# Sheet2.net
KiCad netlist of a schematic drawn in Altium Designer
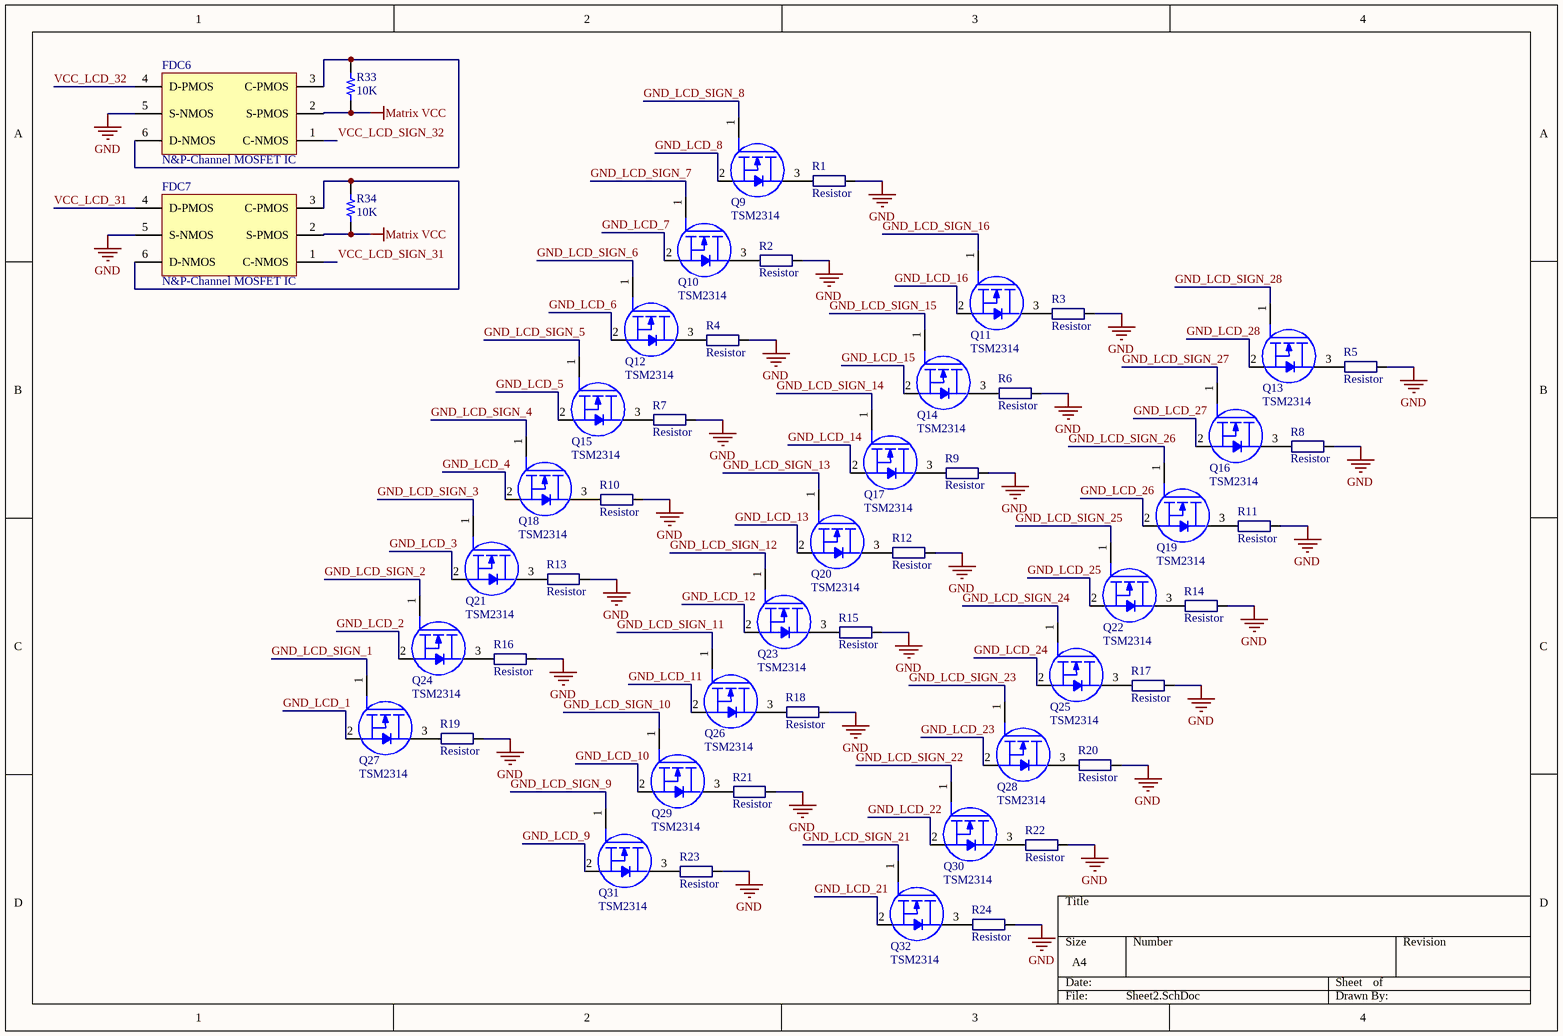
[diagram p0: Sheet2.SchDoc]

(export (version "E")
  (design (tool "Eeschema 10.0.6"))
  (components
    (comp (ref "FDC6")
      (value "N&P-Channel MOSFET IC")
      (footprint "SSOT-6")
      (libsource (lib "IC Chips") (part "FDC633C"))
    )
    (comp (ref "FDC7")
      (value "N&P-Channel MOSFET IC")
      (footprint "SSOT-6")
      (libsource (lib "IC Chips") (part "FDC633C"))
    )
    (comp (ref "Q9")
      (value "TSM2314")
      (footprint "SOT95P280X130-3N")
      (description "N-Channel MOSFET")
      (libsource (lib "OVLib") (part "MOSFET_N_GSD"))
    )
    (comp (ref "Q10")
      (value "TSM2314")
      (footprint "SOT95P280X130-3N")
      (description "N-Channel MOSFET")
      (libsource (lib "OVLib") (part "MOSFET_N_GSD"))
    )
    (comp (ref "Q11")
      (value "TSM2314")
      (footprint "SOT95P280X130-3N")
      (description "N-Channel MOSFET")
      (libsource (lib "OVLib") (part "MOSFET_N_GSD"))
    )
    (comp (ref "Q12")
      (value "TSM2314")
      (footprint "SOT95P280X130-3N")
      (description "N-Channel MOSFET")
      (libsource (lib "OVLib") (part "MOSFET_N_GSD"))
    )
    (comp (ref "Q13")
      (value "TSM2314")
      (footprint "SOT95P280X130-3N")
      (description "N-Channel MOSFET")
      (libsource (lib "OVLib") (part "MOSFET_N_GSD"))
    )
    (comp (ref "Q14")
      (value "TSM2314")
      (footprint "SOT95P280X130-3N")
      (description "N-Channel MOSFET")
      (libsource (lib "OVLib") (part "MOSFET_N_GSD"))
    )
    (comp (ref "Q15")
      (value "TSM2314")
      (footprint "SOT95P280X130-3N")
      (description "N-Channel MOSFET")
      (libsource (lib "OVLib") (part "MOSFET_N_GSD"))
    )
    (comp (ref "Q16")
      (value "TSM2314")
      (footprint "SOT95P280X130-3N")
      (description "N-Channel MOSFET")
      (libsource (lib "OVLib") (part "MOSFET_N_GSD"))
    )
    (comp (ref "Q17")
      (value "TSM2314")
      (footprint "SOT95P280X130-3N")
      (description "N-Channel MOSFET")
      (libsource (lib "OVLib") (part "MOSFET_N_GSD"))
    )
    (comp (ref "Q18")
      (value "TSM2314")
      (footprint "SOT95P280X130-3N")
      (description "N-Channel MOSFET")
      (libsource (lib "OVLib") (part "MOSFET_N_GSD"))
    )
    (comp (ref "Q19")
      (value "TSM2314")
      (footprint "SOT95P280X130-3N")
      (description "N-Channel MOSFET")
      (libsource (lib "OVLib") (part "MOSFET_N_GSD"))
    )
    (comp (ref "Q20")
      (value "TSM2314")
      (footprint "SOT95P280X130-3N")
      (description "N-Channel MOSFET")
      (libsource (lib "OVLib") (part "MOSFET_N_GSD"))
    )
    (comp (ref "Q21")
      (value "TSM2314")
      (footprint "SOT95P280X130-3N")
      (description "N-Channel MOSFET")
      (libsource (lib "OVLib") (part "MOSFET_N_GSD"))
    )
    (comp (ref "Q22")
      (value "TSM2314")
      (footprint "SOT95P280X130-3N")
      (description "N-Channel MOSFET")
      (libsource (lib "OVLib") (part "MOSFET_N_GSD"))
    )
    (comp (ref "Q23")
      (value "TSM2314")
      (footprint "SOT95P280X130-3N")
      (description "N-Channel MOSFET")
      (libsource (lib "OVLib") (part "MOSFET_N_GSD"))
    )
    (comp (ref "Q24")
      (value "TSM2314")
      (footprint "SOT95P280X130-3N")
      (description "N-Channel MOSFET")
      (libsource (lib "OVLib") (part "MOSFET_N_GSD"))
    )
    (comp (ref "Q25")
      (value "TSM2314")
      (footprint "SOT95P280X130-3N")
      (description "N-Channel MOSFET")
      (libsource (lib "OVLib") (part "MOSFET_N_GSD"))
    )
    (comp (ref "Q26")
      (value "TSM2314")
      (footprint "SOT95P280X130-3N")
      (description "N-Channel MOSFET")
      (libsource (lib "OVLib") (part "MOSFET_N_GSD"))
    )
    (comp (ref "Q27")
      (value "TSM2314")
      (footprint "SOT95P280X130-3N")
      (description "N-Channel MOSFET")
      (libsource (lib "OVLib") (part "MOSFET_N_GSD"))
    )
    (comp (ref "Q28")
      (value "TSM2314")
      (footprint "SOT95P280X130-3N")
      (description "N-Channel MOSFET")
      (libsource (lib "OVLib") (part "MOSFET_N_GSD"))
    )
    (comp (ref "Q29")
      (value "TSM2314")
      (footprint "SOT95P280X130-3N")
      (description "N-Channel MOSFET")
      (libsource (lib "OVLib") (part "MOSFET_N_GSD"))
    )
    (comp (ref "Q30")
      (value "TSM2314")
      (footprint "SOT95P280X130-3N")
      (description "N-Channel MOSFET")
      (libsource (lib "OVLib") (part "MOSFET_N_GSD"))
    )
    (comp (ref "Q31")
      (value "TSM2314")
      (footprint "SOT95P280X130-3N")
      (description "N-Channel MOSFET")
      (libsource (lib "OVLib") (part "MOSFET_N_GSD"))
    )
    (comp (ref "Q32")
      (value "TSM2314")
      (footprint "SOT95P280X130-3N")
      (description "N-Channel MOSFET")
      (libsource (lib "OVLib") (part "MOSFET_N_GSD"))
    )
    (comp (ref "R1")
      (value "Resistor")
      (footprint "RESC0603(1608)_N")
      (libsource (lib "Resistor") (part "Resistor"))
    )
    (comp (ref "R2")
      (value "Resistor")
      (footprint "RESC0603(1608)_N")
      (libsource (lib "Resistor") (part "Resistor"))
    )
    (comp (ref "R3")
      (value "Resistor")
      (footprint "RESC0603(1608)_N")
      (libsource (lib "Resistor") (part "Resistor"))
    )
    (comp (ref "R4")
      (value "Resistor")
      (footprint "RESC0603(1608)_N")
      (libsource (lib "Resistor") (part "Resistor"))
    )
    (comp (ref "R5")
      (value "Resistor")
      (footprint "RESC0603(1608)_N")
      (libsource (lib "Resistor") (part "Resistor"))
    )
    (comp (ref "R6")
      (value "Resistor")
      (footprint "RESC0603(1608)_N")
      (libsource (lib "Resistor") (part "Resistor"))
    )
    (comp (ref "R7")
      (value "Resistor")
      (footprint "RESC0603(1608)_N")
      (libsource (lib "Resistor") (part "Resistor"))
    )
    (comp (ref "R8")
      (value "Resistor")
      (footprint "RESC0603(1608)_N")
      (libsource (lib "Resistor") (part "Resistor"))
    )
    (comp (ref "R9")
      (value "Resistor")
      (footprint "RESC0603(1608)_N")
      (libsource (lib "Resistor") (part "Resistor"))
    )
    (comp (ref "R10")
      (value "Resistor")
      (footprint "RESC0603(1608)_N")
      (libsource (lib "Resistor") (part "Resistor"))
    )
    (comp (ref "R11")
      (value "Resistor")
      (footprint "RESC0603(1608)_N")
      (libsource (lib "Resistor") (part "Resistor"))
    )
    (comp (ref "R12")
      (value "Resistor")
      (footprint "RESC0603(1608)_N")
      (libsource (lib "Resistor") (part "Resistor"))
    )
    (comp (ref "R13")
      (value "Resistor")
      (footprint "RESC0603(1608)_N")
      (libsource (lib "Resistor") (part "Resistor"))
    )
    (comp (ref "R14")
      (value "Resistor")
      (footprint "RESC0603(1608)_N")
      (libsource (lib "Resistor") (part "Resistor"))
    )
    (comp (ref "R15")
      (value "Resistor")
      (footprint "RESC0603(1608)_N")
      (libsource (lib "Resistor") (part "Resistor"))
    )
    (comp (ref "R16")
      (value "Resistor")
      (footprint "RESC0603(1608)_N")
      (libsource (lib "Resistor") (part "Resistor"))
    )
    (comp (ref "R17")
      (value "Resistor")
      (footprint "RESC0603(1608)_N")
      (libsource (lib "Resistor") (part "Resistor"))
    )
    (comp (ref "R18")
      (value "Resistor")
      (footprint "RESC0603(1608)_N")
      (libsource (lib "Resistor") (part "Resistor"))
    )
    (comp (ref "R19")
      (value "Resistor")
      (footprint "RESC0603(1608)_N")
      (libsource (lib "Resistor") (part "Resistor"))
    )
    (comp (ref "R20")
      (value "Resistor")
      (footprint "RESC0603(1608)_N")
      (libsource (lib "Resistor") (part "Resistor"))
    )
    (comp (ref "R21")
      (value "Resistor")
      (footprint "RESC0603(1608)_N")
      (libsource (lib "Resistor") (part "Resistor"))
    )
    (comp (ref "R22")
      (value "Resistor")
      (footprint "RESC0603(1608)_N")
      (libsource (lib "Resistor") (part "Resistor"))
    )
    (comp (ref "R23")
      (value "Resistor")
      (footprint "RESC0603(1608)_N")
      (libsource (lib "Resistor") (part "Resistor"))
    )
    (comp (ref "R24")
      (value "Resistor")
      (footprint "RESC0603(1608)_N")
      (libsource (lib "Resistor") (part "Resistor"))
    )
    (comp (ref "R33")
      (value "10K")
      (footprint "RES 0603/1608")
      (description "RES SMD 232 OHM 1% 1/10W 0603")
      (fields (field (name "PART NUMBER") "ERJ-3EKF2320V"))
      (libsource (lib "Celestial Library Database") (part "Resistor"))
    )
    (comp (ref "R34")
      (value "10K")
      (footprint "RES 0603/1608")
      (description "RES SMD 232 OHM 1% 1/10W 0603")
      (fields (field (name "PART NUMBER") "ERJ-3EKF2320V"))
      (libsource (lib "Celestial Library Database") (part "Resistor"))
    )
  )
  (nets
    (net (code "1") (name "/GND_LCD_1") (class "Default")
      (node (ref "Q27") (pin "2") (pinfunction "Source_2") (pintype "passive"))
    )
    (net (code "2") (name "/GND_LCD_2") (class "Default")
      (node (ref "Q24") (pin "2") (pinfunction "Source_2") (pintype "passive"))
    )
    (net (code "3") (name "/GND_LCD_3") (class "Default")
      (node (ref "Q21") (pin "2") (pinfunction "Source_2") (pintype "passive"))
    )
    (net (code "4") (name "/GND_LCD_4") (class "Default")
      (node (ref "Q18") (pin "2") (pinfunction "Source_2") (pintype "passive"))
    )
    (net (code "5") (name "/GND_LCD_5") (class "Default")
      (node (ref "Q15") (pin "2") (pinfunction "Source_2") (pintype "passive"))
    )
    (net (code "6") (name "/GND_LCD_6") (class "Default")
      (node (ref "Q12") (pin "2") (pinfunction "Source_2") (pintype "passive"))
    )
    (net (code "7") (name "/GND_LCD_7") (class "Default")
      (node (ref "Q10") (pin "2") (pinfunction "Source_2") (pintype "passive"))
    )
    (net (code "8") (name "/GND_LCD_8") (class "Default")
      (node (ref "Q9") (pin "2") (pinfunction "Source_2") (pintype "passive"))
    )
    (net (code "9") (name "/GND_LCD_9") (class "Default")
      (node (ref "Q31") (pin "2") (pinfunction "Source_2") (pintype "passive"))
    )
    (net (code "10") (name "/GND_LCD_10") (class "Default")
      (node (ref "Q29") (pin "2") (pinfunction "Source_2") (pintype "passive"))
    )
    (net (code "11") (name "/GND_LCD_11") (class "Default")
      (node (ref "Q26") (pin "2") (pinfunction "Source_2") (pintype "passive"))
    )
    (net (code "12") (name "/GND_LCD_12") (class "Default")
      (node (ref "Q23") (pin "2") (pinfunction "Source_2") (pintype "passive"))
    )
    (net (code "13") (name "/GND_LCD_13") (class "Default")
      (node (ref "Q20") (pin "2") (pinfunction "Source_2") (pintype "passive"))
    )
    (net (code "14") (name "/GND_LCD_14") (class "Default")
      (node (ref "Q17") (pin "2") (pinfunction "Source_2") (pintype "passive"))
    )
    (net (code "15") (name "/GND_LCD_15") (class "Default")
      (node (ref "Q14") (pin "2") (pinfunction "Source_2") (pintype "passive"))
    )
    (net (code "16") (name "/GND_LCD_16") (class "Default")
      (node (ref "Q11") (pin "2") (pinfunction "Source_2") (pintype "passive"))
    )
    (net (code "17") (name "/GND_LCD_21") (class "Default")
      (node (ref "Q32") (pin "2") (pinfunction "Source_2") (pintype "passive"))
    )
    (net (code "18") (name "/GND_LCD_22") (class "Default")
      (node (ref "Q30") (pin "2") (pinfunction "Source_2") (pintype "passive"))
    )
    (net (code "19") (name "/GND_LCD_23") (class "Default")
      (node (ref "Q28") (pin "2") (pinfunction "Source_2") (pintype "passive"))
    )
    (net (code "20") (name "/GND_LCD_24") (class "Default")
      (node (ref "Q25") (pin "2") (pinfunction "Source_2") (pintype "passive"))
    )
    (net (code "21") (name "/GND_LCD_25") (class "Default")
      (node (ref "Q22") (pin "2") (pinfunction "Source_2") (pintype "passive"))
    )
    (net (code "22") (name "/GND_LCD_26") (class "Default")
      (node (ref "Q19") (pin "2") (pinfunction "Source_2") (pintype "passive"))
    )
    (net (code "23") (name "/GND_LCD_27") (class "Default")
      (node (ref "Q16") (pin "2") (pinfunction "Source_2") (pintype "passive"))
    )
    (net (code "24") (name "/GND_LCD_28") (class "Default")
      (node (ref "Q13") (pin "2") (pinfunction "Source_2") (pintype "passive"))
    )
    (net (code "25") (name "/GND_LCD_SIGN_1") (class "Default")
      (node (ref "Q27") (pin "1") (pinfunction "Gate_1") (pintype "passive"))
    )
    (net (code "26") (name "/GND_LCD_SIGN_2") (class "Default")
      (node (ref "Q24") (pin "1") (pinfunction "Gate_1") (pintype "passive"))
    )
    (net (code "27") (name "/GND_LCD_SIGN_3") (class "Default")
      (node (ref "Q21") (pin "1") (pinfunction "Gate_1") (pintype "passive"))
    )
    (net (code "28") (name "/GND_LCD_SIGN_4") (class "Default")
      (node (ref "Q18") (pin "1") (pinfunction "Gate_1") (pintype "passive"))
    )
    (net (code "29") (name "/GND_LCD_SIGN_5") (class "Default")
      (node (ref "Q15") (pin "1") (pinfunction "Gate_1") (pintype "passive"))
    )
    (net (code "30") (name "/GND_LCD_SIGN_6") (class "Default")
      (node (ref "Q12") (pin "1") (pinfunction "Gate_1") (pintype "passive"))
    )
    (net (code "31") (name "/GND_LCD_SIGN_7") (class "Default")
      (node (ref "Q10") (pin "1") (pinfunction "Gate_1") (pintype "passive"))
    )
    (net (code "32") (name "/GND_LCD_SIGN_8") (class "Default")
      (node (ref "Q9") (pin "1") (pinfunction "Gate_1") (pintype "passive"))
    )
    (net (code "33") (name "/GND_LCD_SIGN_9") (class "Default")
      (node (ref "Q31") (pin "1") (pinfunction "Gate_1") (pintype "passive"))
    )
    (net (code "34") (name "/GND_LCD_SIGN_10") (class "Default")
      (node (ref "Q29") (pin "1") (pinfunction "Gate_1") (pintype "passive"))
    )
    (net (code "35") (name "/GND_LCD_SIGN_11") (class "Default")
      (node (ref "Q26") (pin "1") (pinfunction "Gate_1") (pintype "passive"))
    )
    (net (code "36") (name "/GND_LCD_SIGN_12") (class "Default")
      (node (ref "Q23") (pin "1") (pinfunction "Gate_1") (pintype "passive"))
    )
    (net (code "37") (name "/GND_LCD_SIGN_13") (class "Default")
      (node (ref "Q20") (pin "1") (pinfunction "Gate_1") (pintype "passive"))
    )
    (net (code "38") (name "/GND_LCD_SIGN_14") (class "Default")
      (node (ref "Q17") (pin "1") (pinfunction "Gate_1") (pintype "passive"))
    )
    (net (code "39") (name "/GND_LCD_SIGN_15") (class "Default")
      (node (ref "Q14") (pin "1") (pinfunction "Gate_1") (pintype "passive"))
    )
    (net (code "40") (name "/GND_LCD_SIGN_16") (class "Default")
      (node (ref "Q11") (pin "1") (pinfunction "Gate_1") (pintype "passive"))
    )
    (net (code "41") (name "/GND_LCD_SIGN_21") (class "Default")
      (node (ref "Q32") (pin "1") (pinfunction "Gate_1") (pintype "passive"))
    )
    (net (code "42") (name "/GND_LCD_SIGN_22") (class "Default")
      (node (ref "Q30") (pin "1") (pinfunction "Gate_1") (pintype "passive"))
    )
    (net (code "43") (name "/GND_LCD_SIGN_23") (class "Default")
      (node (ref "Q28") (pin "1") (pinfunction "Gate_1") (pintype "passive"))
    )
    (net (code "44") (name "/GND_LCD_SIGN_24") (class "Default")
      (node (ref "Q25") (pin "1") (pinfunction "Gate_1") (pintype "passive"))
    )
    (net (code "45") (name "/GND_LCD_SIGN_25") (class "Default")
      (node (ref "Q22") (pin "1") (pinfunction "Gate_1") (pintype "passive"))
    )
    (net (code "46") (name "/GND_LCD_SIGN_26") (class "Default")
      (node (ref "Q19") (pin "1") (pinfunction "Gate_1") (pintype "passive"))
    )
    (net (code "47") (name "/GND_LCD_SIGN_27") (class "Default")
      (node (ref "Q16") (pin "1") (pinfunction "Gate_1") (pintype "passive"))
    )
    (net (code "48") (name "/GND_LCD_SIGN_28") (class "Default")
      (node (ref "Q13") (pin "1") (pinfunction "Gate_1") (pintype "passive"))
    )
    (net (code "49") (name "/VCC_LCD_31") (class "Default")
      (node (ref "FDC7") (pin "4") (pinfunction "D-PMOS_4") (pintype "passive"))
    )
    (net (code "50") (name "/VCC_LCD_32") (class "Default")
      (node (ref "FDC6") (pin "4") (pinfunction "D-PMOS_4") (pintype "passive"))
    )
    (net (code "53") (name "/VCC_LCD_SIGN_31") (class "Default")
      (node (ref "FDC7") (pin "1") (pinfunction "C-NMOS_1") (pintype "passive"))
    )
    (net (code "54") (name "/VCC_LCD_SIGN_32") (class "Default")
      (node (ref "FDC6") (pin "1") (pinfunction "C-NMOS_1") (pintype "passive"))
    )
    (net (code "55") (name "GND") (class "Default")
      (node (ref "FDC6") (pin "5") (pinfunction "S-NMOS_5") (pintype "passive"))
      (node (ref "FDC7") (pin "5") (pinfunction "S-NMOS_5") (pintype "passive"))
      (node (ref "R1") (pin "2") (pinfunction "2_2") (pintype "passive"))
      (node (ref "R10") (pin "2") (pinfunction "2_2") (pintype "passive"))
      (node (ref "R11") (pin "2") (pinfunction "2_2") (pintype "passive"))
      (node (ref "R12") (pin "2") (pinfunction "2_2") (pintype "passive"))
      (node (ref "R13") (pin "2") (pinfunction "2_2") (pintype "passive"))
      (node (ref "R14") (pin "2") (pinfunction "2_2") (pintype "passive"))
      (node (ref "R15") (pin "2") (pinfunction "2_2") (pintype "passive"))
      (node (ref "R16") (pin "2") (pinfunction "2_2") (pintype "passive"))
      (node (ref "R17") (pin "2") (pinfunction "2_2") (pintype "passive"))
      (node (ref "R18") (pin "2") (pinfunction "2_2") (pintype "passive"))
      (node (ref "R19") (pin "2") (pinfunction "2_2") (pintype "passive"))
      (node (ref "R2") (pin "2") (pinfunction "2_2") (pintype "passive"))
      (node (ref "R20") (pin "2") (pinfunction "2_2") (pintype "passive"))
      (node (ref "R21") (pin "2") (pinfunction "2_2") (pintype "passive"))
      (node (ref "R22") (pin "2") (pinfunction "2_2") (pintype "passive"))
      (node (ref "R23") (pin "2") (pinfunction "2_2") (pintype "passive"))
      (node (ref "R24") (pin "2") (pinfunction "2_2") (pintype "passive"))
      (node (ref "R3") (pin "2") (pinfunction "2_2") (pintype "passive"))
      (node (ref "R4") (pin "2") (pinfunction "2_2") (pintype "passive"))
      (node (ref "R5") (pin "2") (pinfunction "2_2") (pintype "passive"))
      (node (ref "R6") (pin "2") (pinfunction "2_2") (pintype "passive"))
      (node (ref "R7") (pin "2") (pinfunction "2_2") (pintype "passive"))
      (node (ref "R8") (pin "2") (pinfunction "2_2") (pintype "passive"))
      (node (ref "R9") (pin "2") (pinfunction "2_2") (pintype "passive"))
    )
    (net (code "56") (name "Matrix VCC") (class "Default")
      (node (ref "FDC6") (pin "2") (pinfunction "S-PMOS_2") (pintype "passive"))
      (node (ref "FDC7") (pin "2") (pinfunction "S-PMOS_2") (pintype "passive"))
      (node (ref "R33") (pin "1") (pinfunction "1_1") (pintype "passive"))
      (node (ref "R34") (pin "1") (pinfunction "1_1") (pintype "passive"))
    )
    (net (code "57") (name "Net-(FDC6-C-PMOS)") (class "Default")
      (node (ref "FDC6") (pin "3") (pinfunction "C-PMOS_3") (pintype "passive"))
      (node (ref "FDC6") (pin "6") (pinfunction "D-NMOS_6") (pintype "passive"))
      (node (ref "R33") (pin "2") (pinfunction "2_2") (pintype "passive"))
    )
    (net (code "58") (name "Net-(FDC7-C-PMOS)") (class "Default")
      (node (ref "FDC7") (pin "3") (pinfunction "C-PMOS_3") (pintype "passive"))
      (node (ref "FDC7") (pin "6") (pinfunction "D-NMOS_6") (pintype "passive"))
      (node (ref "R34") (pin "2") (pinfunction "2_2") (pintype "passive"))
    )
    (net (code "59") (name "Net-(Q9-Drain)") (class "Default")
      (node (ref "Q9") (pin "3") (pinfunction "Drain_3") (pintype "passive"))
      (node (ref "R1") (pin "1") (pinfunction "1_1") (pintype "passive"))
    )
    (net (code "60") (name "Net-(Q10-Drain)") (class "Default")
      (node (ref "Q10") (pin "3") (pinfunction "Drain_3") (pintype "passive"))
      (node (ref "R2") (pin "1") (pinfunction "1_1") (pintype "passive"))
    )
    (net (code "61") (name "Net-(Q11-Drain)") (class "Default")
      (node (ref "Q11") (pin "3") (pinfunction "Drain_3") (pintype "passive"))
      (node (ref "R3") (pin "1") (pinfunction "1_1") (pintype "passive"))
    )
    (net (code "62") (name "Net-(Q12-Drain)") (class "Default")
      (node (ref "Q12") (pin "3") (pinfunction "Drain_3") (pintype "passive"))
      (node (ref "R4") (pin "1") (pinfunction "1_1") (pintype "passive"))
    )
    (net (code "63") (name "Net-(Q13-Drain)") (class "Default")
      (node (ref "Q13") (pin "3") (pinfunction "Drain_3") (pintype "passive"))
      (node (ref "R5") (pin "1") (pinfunction "1_1") (pintype "passive"))
    )
    (net (code "64") (name "Net-(Q14-Drain)") (class "Default")
      (node (ref "Q14") (pin "3") (pinfunction "Drain_3") (pintype "passive"))
      (node (ref "R6") (pin "1") (pinfunction "1_1") (pintype "passive"))
    )
    (net (code "65") (name "Net-(Q15-Drain)") (class "Default")
      (node (ref "Q15") (pin "3") (pinfunction "Drain_3") (pintype "passive"))
      (node (ref "R7") (pin "1") (pinfunction "1_1") (pintype "passive"))
    )
    (net (code "66") (name "Net-(Q16-Drain)") (class "Default")
      (node (ref "Q16") (pin "3") (pinfunction "Drain_3") (pintype "passive"))
      (node (ref "R8") (pin "1") (pinfunction "1_1") (pintype "passive"))
    )
    (net (code "67") (name "Net-(Q17-Drain)") (class "Default")
      (node (ref "Q17") (pin "3") (pinfunction "Drain_3") (pintype "passive"))
      (node (ref "R9") (pin "1") (pinfunction "1_1") (pintype "passive"))
    )
    (net (code "68") (name "Net-(Q18-Drain)") (class "Default")
      (node (ref "Q18") (pin "3") (pinfunction "Drain_3") (pintype "passive"))
      (node (ref "R10") (pin "1") (pinfunction "1_1") (pintype "passive"))
    )
    (net (code "69") (name "Net-(Q19-Drain)") (class "Default")
      (node (ref "Q19") (pin "3") (pinfunction "Drain_3") (pintype "passive"))
      (node (ref "R11") (pin "1") (pinfunction "1_1") (pintype "passive"))
    )
    (net (code "70") (name "Net-(Q20-Drain)") (class "Default")
      (node (ref "Q20") (pin "3") (pinfunction "Drain_3") (pintype "passive"))
      (node (ref "R12") (pin "1") (pinfunction "1_1") (pintype "passive"))
    )
    (net (code "71") (name "Net-(Q21-Drain)") (class "Default")
      (node (ref "Q21") (pin "3") (pinfunction "Drain_3") (pintype "passive"))
      (node (ref "R13") (pin "1") (pinfunction "1_1") (pintype "passive"))
    )
    (net (code "72") (name "Net-(Q22-Drain)") (class "Default")
      (node (ref "Q22") (pin "3") (pinfunction "Drain_3") (pintype "passive"))
      (node (ref "R14") (pin "1") (pinfunction "1_1") (pintype "passive"))
    )
    (net (code "73") (name "Net-(Q23-Drain)") (class "Default")
      (node (ref "Q23") (pin "3") (pinfunction "Drain_3") (pintype "passive"))
      (node (ref "R15") (pin "1") (pinfunction "1_1") (pintype "passive"))
    )
    (net (code "74") (name "Net-(Q24-Drain)") (class "Default")
      (node (ref "Q24") (pin "3") (pinfunction "Drain_3") (pintype "passive"))
      (node (ref "R16") (pin "1") (pinfunction "1_1") (pintype "passive"))
    )
    (net (code "75") (name "Net-(Q25-Drain)") (class "Default")
      (node (ref "Q25") (pin "3") (pinfunction "Drain_3") (pintype "passive"))
      (node (ref "R17") (pin "1") (pinfunction "1_1") (pintype "passive"))
    )
    (net (code "76") (name "Net-(Q26-Drain)") (class "Default")
      (node (ref "Q26") (pin "3") (pinfunction "Drain_3") (pintype "passive"))
      (node (ref "R18") (pin "1") (pinfunction "1_1") (pintype "passive"))
    )
    (net (code "77") (name "Net-(Q27-Drain)") (class "Default")
      (node (ref "Q27") (pin "3") (pinfunction "Drain_3") (pintype "passive"))
      (node (ref "R19") (pin "1") (pinfunction "1_1") (pintype "passive"))
    )
    (net (code "78") (name "Net-(Q28-Drain)") (class "Default")
      (node (ref "Q28") (pin "3") (pinfunction "Drain_3") (pintype "passive"))
      (node (ref "R20") (pin "1") (pinfunction "1_1") (pintype "passive"))
    )
    (net (code "79") (name "Net-(Q29-Drain)") (class "Default")
      (node (ref "Q29") (pin "3") (pinfunction "Drain_3") (pintype "passive"))
      (node (ref "R21") (pin "1") (pinfunction "1_1") (pintype "passive"))
    )
    (net (code "80") (name "Net-(Q30-Drain)") (class "Default")
      (node (ref "Q30") (pin "3") (pinfunction "Drain_3") (pintype "passive"))
      (node (ref "R22") (pin "1") (pinfunction "1_1") (pintype "passive"))
    )
    (net (code "81") (name "Net-(Q31-Drain)") (class "Default")
      (node (ref "Q31") (pin "3") (pinfunction "Drain_3") (pintype "passive"))
      (node (ref "R23") (pin "1") (pinfunction "1_1") (pintype "passive"))
    )
    (net (code "82") (name "Net-(Q32-Drain)") (class "Default")
      (node (ref "Q32") (pin "3") (pinfunction "Drain_3") (pintype "passive"))
      (node (ref "R24") (pin "1") (pinfunction "1_1") (pintype "passive"))
    )
  )
)
